# DUT_Platform.net
KiCad netlist of a schematic drawn in Altium Designer
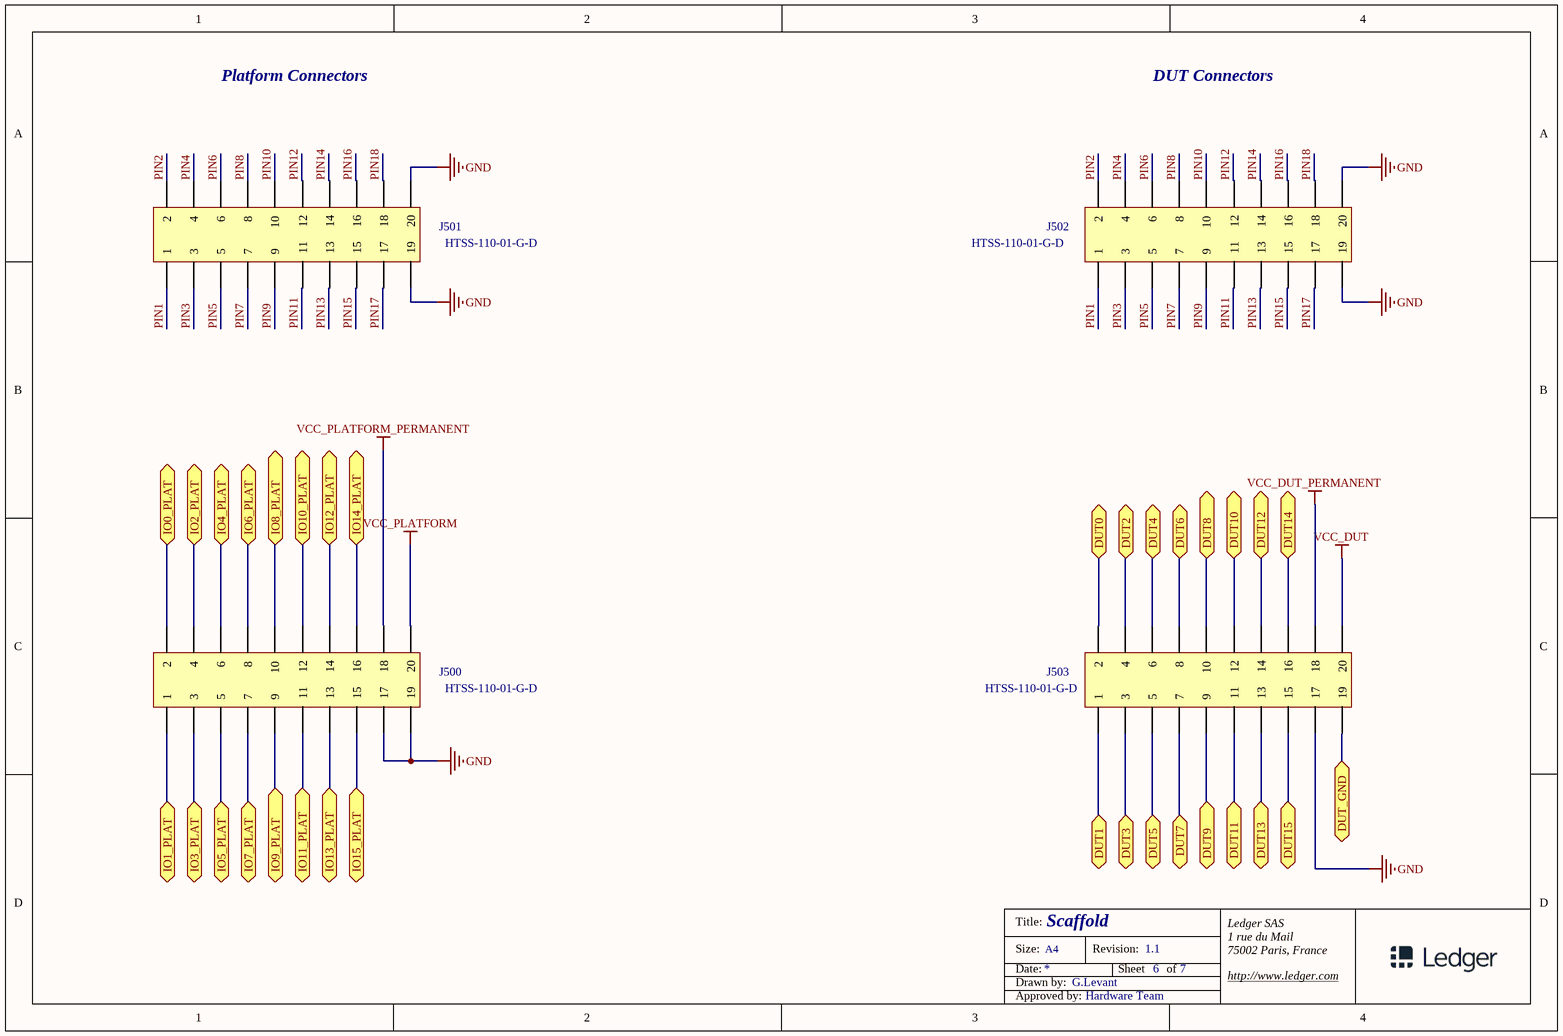
[diagram p0: DUT_Platform.SchDoc]

(export (version "E")
  (design (tool "Eeschema 10.0.6"))
  (components
    (comp (ref "J500")
      (value "HTSS-110-01-G-D")
      (footprint "SAMTEC_HTSS-110-01-G-D")
      (description "Connector - Header - 20 Pins - Dual row - Shrouded - Male")
      (fields (field (name "MANUFACTURER") "Samtec"))
      (libsource (lib "Ledger_Dev") (part "Connector - Header - 20 Pins - Dual row - Shrouded - Male"))
    )
    (comp (ref "J501")
      (value "HTSS-110-01-G-D")
      (footprint "SAMTEC_HTSS-110-01-G-D")
      (description "Connector - Header - 20 Pins - Dual row - Shrouded - Male")
      (fields (field (name "MANUFACTURER") "Samtec"))
      (libsource (lib "Ledger_Dev") (part "Connector - Header - 20 Pins - Dual row - Shrouded - Male"))
    )
    (comp (ref "J502")
      (value "HTSS-110-01-G-D")
      (footprint "SAMTEC_HTSS-110-01-G-D")
      (description "Connector - Header - 20 Pins - Dual row - Shrouded - Male")
      (fields (field (name "MANUFACTURER") "Samtec"))
      (libsource (lib "Ledger_Dev") (part "Connector - Header - 20 Pins - Dual row - Shrouded - Male"))
    )
    (comp (ref "J503")
      (value "HTSS-110-01-G-D")
      (footprint "SAMTEC_HTSS-110-01-G-D")
      (description "Connector - Header - 20 Pins - Dual row - Shrouded - Male")
      (fields (field (name "MANUFACTURER") "Samtec"))
      (libsource (lib "Ledger_Dev") (part "Connector - Header - 20 Pins - Dual row - Shrouded - Male"))
    )
  )
  (nets
    (net (code "1") (name "/DUT0") (class "Default")
      (node (ref "J503") (pin "2") (pinfunction "2_2") (pintype "passive"))
    )
    (net (code "2") (name "/DUT1") (class "Default")
      (node (ref "J503") (pin "1") (pinfunction "1_1") (pintype "passive"))
    )
    (net (code "3") (name "/DUT2") (class "Default")
      (node (ref "J503") (pin "4") (pinfunction "4_4") (pintype "passive"))
    )
    (net (code "4") (name "/DUT3") (class "Default")
      (node (ref "J503") (pin "3") (pinfunction "3_3") (pintype "passive"))
    )
    (net (code "5") (name "/DUT4") (class "Default")
      (node (ref "J503") (pin "6") (pinfunction "6_6") (pintype "passive"))
    )
    (net (code "6") (name "/DUT5") (class "Default")
      (node (ref "J503") (pin "5") (pinfunction "5_5") (pintype "passive"))
    )
    (net (code "7") (name "/DUT6") (class "Default")
      (node (ref "J503") (pin "8") (pinfunction "8_8") (pintype "passive"))
    )
    (net (code "8") (name "/DUT7") (class "Default")
      (node (ref "J503") (pin "7") (pinfunction "7_7") (pintype "passive"))
    )
    (net (code "9") (name "/DUT8") (class "Default")
      (node (ref "J503") (pin "10") (pinfunction "10_10") (pintype "passive"))
    )
    (net (code "10") (name "/DUT9") (class "Default")
      (node (ref "J503") (pin "9") (pinfunction "9_9") (pintype "passive"))
    )
    (net (code "11") (name "/DUT10") (class "Default")
      (node (ref "J503") (pin "12") (pinfunction "12_12") (pintype "passive"))
    )
    (net (code "12") (name "/DUT11") (class "Default")
      (node (ref "J503") (pin "11") (pinfunction "11_11") (pintype "passive"))
    )
    (net (code "13") (name "/DUT12") (class "Default")
      (node (ref "J503") (pin "14") (pinfunction "14_14") (pintype "passive"))
    )
    (net (code "14") (name "/DUT13") (class "Default")
      (node (ref "J503") (pin "13") (pinfunction "13_13") (pintype "passive"))
    )
    (net (code "15") (name "/DUT14") (class "Default")
      (node (ref "J503") (pin "16") (pinfunction "16_16") (pintype "passive"))
    )
    (net (code "16") (name "/DUT15") (class "Default")
      (node (ref "J503") (pin "15") (pinfunction "15_15") (pintype "passive"))
    )
    (net (code "17") (name "/DUT_GND") (class "Default")
      (node (ref "J503") (pin "19") (pinfunction "19_19") (pintype "passive"))
    )
    (net (code "18") (name "/IO0_PLAT") (class "Default")
      (node (ref "J500") (pin "2") (pinfunction "2_2") (pintype "passive"))
    )
    (net (code "19") (name "/IO1_PLAT") (class "Default")
      (node (ref "J500") (pin "1") (pinfunction "1_1") (pintype "passive"))
    )
    (net (code "20") (name "/IO2_PLAT") (class "Default")
      (node (ref "J500") (pin "4") (pinfunction "4_4") (pintype "passive"))
    )
    (net (code "21") (name "/IO3_PLAT") (class "Default")
      (node (ref "J500") (pin "3") (pinfunction "3_3") (pintype "passive"))
    )
    (net (code "22") (name "/IO4_PLAT") (class "Default")
      (node (ref "J500") (pin "6") (pinfunction "6_6") (pintype "passive"))
    )
    (net (code "23") (name "/IO5_PLAT") (class "Default")
      (node (ref "J500") (pin "5") (pinfunction "5_5") (pintype "passive"))
    )
    (net (code "24") (name "/IO6_PLAT") (class "Default")
      (node (ref "J500") (pin "8") (pinfunction "8_8") (pintype "passive"))
    )
    (net (code "25") (name "/IO7_PLAT") (class "Default")
      (node (ref "J500") (pin "7") (pinfunction "7_7") (pintype "passive"))
    )
    (net (code "26") (name "/IO8_PLAT") (class "Default")
      (node (ref "J500") (pin "10") (pinfunction "10_10") (pintype "passive"))
    )
    (net (code "27") (name "/IO9_PLAT") (class "Default")
      (node (ref "J500") (pin "9") (pinfunction "9_9") (pintype "passive"))
    )
    (net (code "28") (name "/IO10_PLAT") (class "Default")
      (node (ref "J500") (pin "12") (pinfunction "12_12") (pintype "passive"))
    )
    (net (code "29") (name "/IO11_PLAT") (class "Default")
      (node (ref "J500") (pin "11") (pinfunction "11_11") (pintype "passive"))
    )
    (net (code "30") (name "/IO12_PLAT") (class "Default")
      (node (ref "J500") (pin "14") (pinfunction "14_14") (pintype "passive"))
    )
    (net (code "31") (name "/IO13_PLAT") (class "Default")
      (node (ref "J500") (pin "13") (pinfunction "13_13") (pintype "passive"))
    )
    (net (code "32") (name "/IO14_PLAT") (class "Default")
      (node (ref "J500") (pin "16") (pinfunction "16_16") (pintype "passive"))
    )
    (net (code "33") (name "/IO15_PLAT") (class "Default")
      (node (ref "J500") (pin "15") (pinfunction "15_15") (pintype "passive"))
    )
    (net (code "34") (name "/PIN1") (class "Default")
      (node (ref "J501") (pin "1") (pinfunction "1_1") (pintype "passive"))
      (node (ref "J502") (pin "1") (pinfunction "1_1") (pintype "passive"))
    )
    (net (code "35") (name "/PIN2") (class "Default")
      (node (ref "J501") (pin "2") (pinfunction "2_2") (pintype "passive"))
      (node (ref "J502") (pin "2") (pinfunction "2_2") (pintype "passive"))
    )
    (net (code "36") (name "/PIN3") (class "Default")
      (node (ref "J501") (pin "3") (pinfunction "3_3") (pintype "passive"))
      (node (ref "J502") (pin "3") (pinfunction "3_3") (pintype "passive"))
    )
    (net (code "37") (name "/PIN4") (class "Default")
      (node (ref "J501") (pin "4") (pinfunction "4_4") (pintype "passive"))
      (node (ref "J502") (pin "4") (pinfunction "4_4") (pintype "passive"))
    )
    (net (code "38") (name "/PIN5") (class "Default")
      (node (ref "J501") (pin "5") (pinfunction "5_5") (pintype "passive"))
      (node (ref "J502") (pin "5") (pinfunction "5_5") (pintype "passive"))
    )
    (net (code "39") (name "/PIN6") (class "Default")
      (node (ref "J501") (pin "6") (pinfunction "6_6") (pintype "passive"))
      (node (ref "J502") (pin "6") (pinfunction "6_6") (pintype "passive"))
    )
    (net (code "40") (name "/PIN7") (class "Default")
      (node (ref "J501") (pin "7") (pinfunction "7_7") (pintype "passive"))
      (node (ref "J502") (pin "7") (pinfunction "7_7") (pintype "passive"))
    )
    (net (code "41") (name "/PIN8") (class "Default")
      (node (ref "J501") (pin "8") (pinfunction "8_8") (pintype "passive"))
      (node (ref "J502") (pin "8") (pinfunction "8_8") (pintype "passive"))
    )
    (net (code "42") (name "/PIN9") (class "Default")
      (node (ref "J501") (pin "9") (pinfunction "9_9") (pintype "passive"))
      (node (ref "J502") (pin "9") (pinfunction "9_9") (pintype "passive"))
    )
    (net (code "43") (name "/PIN10") (class "Default")
      (node (ref "J501") (pin "10") (pinfunction "10_10") (pintype "passive"))
      (node (ref "J502") (pin "10") (pinfunction "10_10") (pintype "passive"))
    )
    (net (code "44") (name "/PIN11") (class "Default")
      (node (ref "J501") (pin "11") (pinfunction "11_11") (pintype "passive"))
      (node (ref "J502") (pin "11") (pinfunction "11_11") (pintype "passive"))
    )
    (net (code "45") (name "/PIN12") (class "Default")
      (node (ref "J501") (pin "12") (pinfunction "12_12") (pintype "passive"))
      (node (ref "J502") (pin "12") (pinfunction "12_12") (pintype "passive"))
    )
    (net (code "46") (name "/PIN13") (class "Default")
      (node (ref "J501") (pin "13") (pinfunction "13_13") (pintype "passive"))
      (node (ref "J502") (pin "13") (pinfunction "13_13") (pintype "passive"))
    )
    (net (code "47") (name "/PIN14") (class "Default")
      (node (ref "J501") (pin "14") (pinfunction "14_14") (pintype "passive"))
      (node (ref "J502") (pin "14") (pinfunction "14_14") (pintype "passive"))
    )
    (net (code "48") (name "/PIN15") (class "Default")
      (node (ref "J501") (pin "15") (pinfunction "15_15") (pintype "passive"))
      (node (ref "J502") (pin "15") (pinfunction "15_15") (pintype "passive"))
    )
    (net (code "49") (name "/PIN16") (class "Default")
      (node (ref "J501") (pin "16") (pinfunction "16_16") (pintype "passive"))
      (node (ref "J502") (pin "16") (pinfunction "16_16") (pintype "passive"))
    )
    (net (code "50") (name "/PIN17") (class "Default")
      (node (ref "J501") (pin "17") (pinfunction "17_17") (pintype "passive"))
      (node (ref "J502") (pin "17") (pinfunction "17_17") (pintype "passive"))
    )
    (net (code "51") (name "/PIN18") (class "Default")
      (node (ref "J501") (pin "18") (pinfunction "18_18") (pintype "passive"))
      (node (ref "J502") (pin "18") (pinfunction "18_18") (pintype "passive"))
    )
    (net (code "52") (name "GND") (class "Default")
      (node (ref "J500") (pin "17") (pinfunction "17_17") (pintype "passive"))
      (node (ref "J500") (pin "19") (pinfunction "19_19") (pintype "passive"))
      (node (ref "J501") (pin "19") (pinfunction "19_19") (pintype "passive"))
      (node (ref "J501") (pin "20") (pinfunction "20_20") (pintype "passive"))
      (node (ref "J502") (pin "19") (pinfunction "19_19") (pintype "passive"))
      (node (ref "J502") (pin "20") (pinfunction "20_20") (pintype "passive"))
      (node (ref "J503") (pin "17") (pinfunction "17_17") (pintype "passive"))
    )
    (net (code "53") (name "VCC_DUT") (class "Default")
      (node (ref "J503") (pin "20") (pinfunction "20_20") (pintype "passive"))
    )
    (net (code "54") (name "VCC_DUT_PERMANENT") (class "Default")
      (node (ref "J503") (pin "18") (pinfunction "18_18") (pintype "passive"))
    )
    (net (code "55") (name "VCC_PLATFORM") (class "Default")
      (node (ref "J500") (pin "20") (pinfunction "20_20") (pintype "passive"))
    )
    (net (code "56") (name "VCC_PLATFORM_PERMANENT") (class "Default")
      (node (ref "J500") (pin "18") (pinfunction "18_18") (pintype "passive"))
    )
  )
)
